# Module_ESP32.net
KiCad netlist of a schematic drawn in Altium Designer
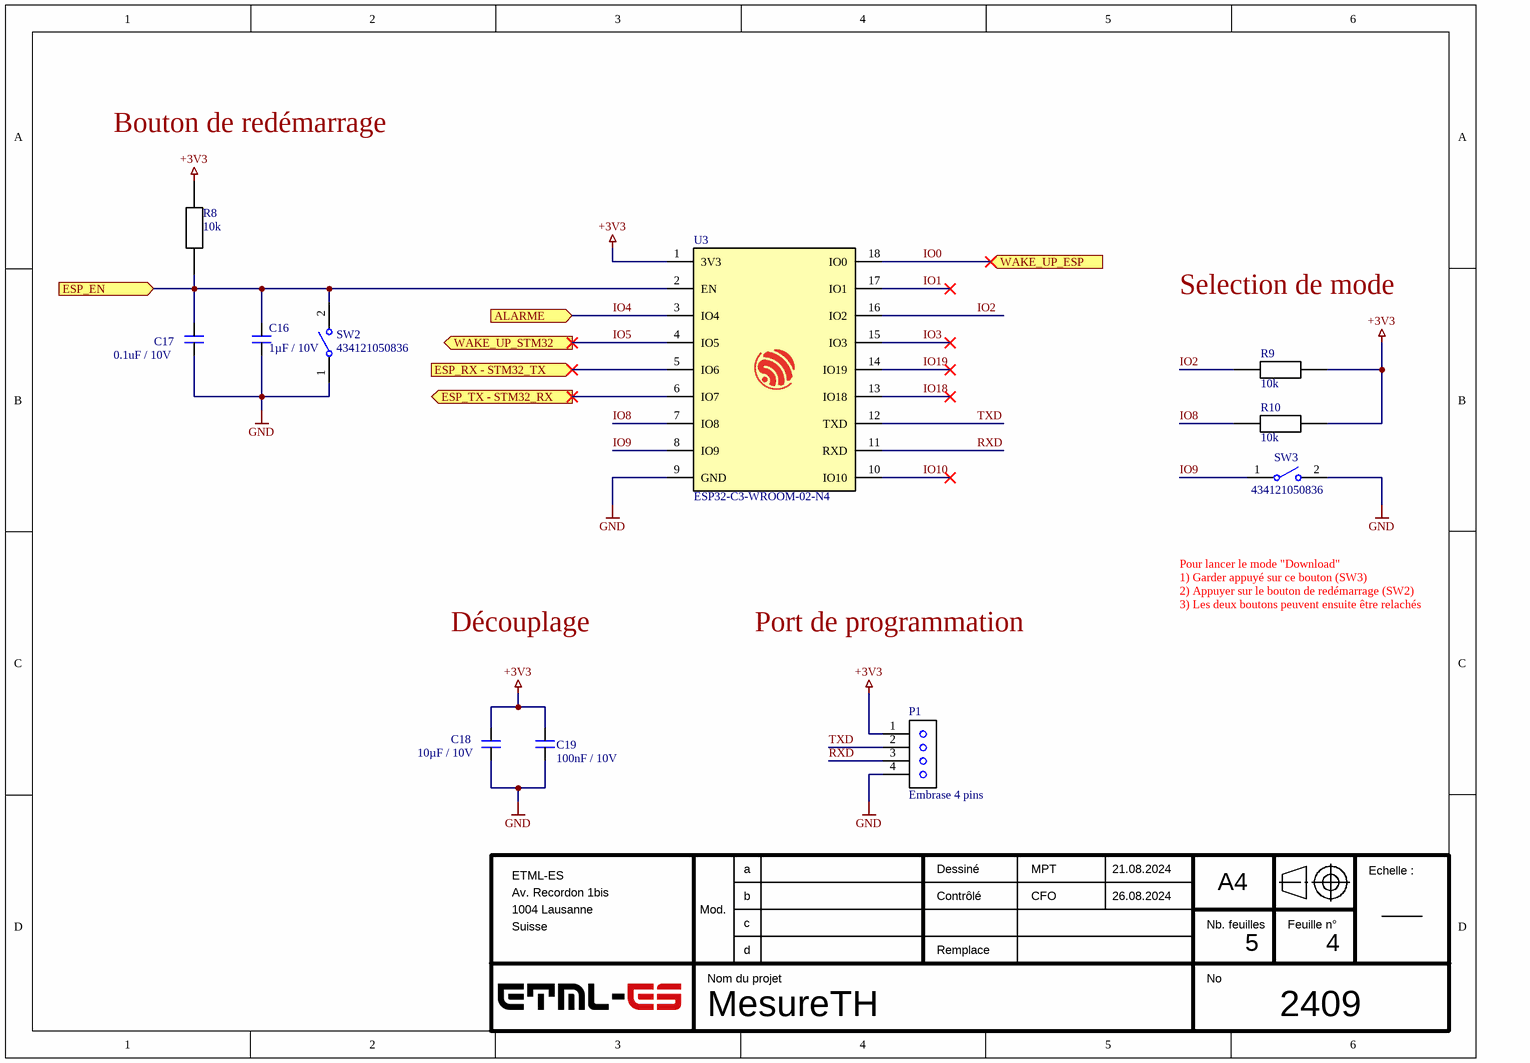
[diagram p0: Module ESP32.SchDoc]

(export (version "E")
  (design (tool "Eeschema 10.0.6"))
  (components
    (comp (ref "C16")
      (value "1µF / 10V")
      (footprint "WCAP-CSGP_0805_L2W1.25H0.8_Wave")
      (libsource (lib "Composants_Projet_2409") (part "CAPA"))
    )
    (comp (ref "C17")
      (value "0.1uF / 10V")
      (footprint "WCAP-CSGP_0805_L2W1.25H0.8_Wave")
      (libsource (lib "Composants_Projet_2409") (part "CAPA"))
    )
    (comp (ref "C18")
      (value "10µF / 10V")
      (footprint "WCAP-CSGP_0805_L2W1.25H0.8_Wave")
      (libsource (lib "Composants_Projet_2409") (part "CAPA"))
    )
    (comp (ref "C19")
      (value "100nF / 10V")
      (footprint "WCAP-CSGP_0805_L2W1.25H0.8_Wave")
      (libsource (lib "Composants_Projet_2409") (part "CAPA"))
    )
    (comp (ref "P1")
      (value "Embrase 4 pins")
      (footprint "1x4")
      (libsource (lib "Composants_Projet_2409") (part "Embrase 4 pins"))
    )
    (comp (ref "R8")
      (value "10k")
      (footprint "WRIS-PSMB_0805_L2W1.25H0.35")
      (libsource (lib "") (part "Resistance_1"))
    )
    (comp (ref "R9")
      (value "10k")
      (footprint "WRIS-PSMB_0805_L2W1.25H0.35")
      (libsource (lib "Composants_Projet_2409") (part "Resistance"))
    )
    (comp (ref "R10")
      (value "10k")
      (footprint "WRIS-PSMB_0805_L2W1.25H0.35")
      (libsource (lib "Composants_Projet_2409") (part "Resistance"))
    )
    (comp (ref "SW2")
      (value "434121050836")
      (footprint "WS-TASV_L6W3.5H5_4341x10508x6")
      (libsource (lib "Altium Content Vault") (part "SPST-NO_2P"))
    )
    (comp (ref "SW3")
      (value "434121050836")
      (footprint "WS-TASV_L6W3.5H5_4341x10508x6")
      (libsource (lib "Altium Content Vault") (part "SPST-NO_2P"))
    )
    (comp (ref "U3")
      (value "ESP32-C3-WROOM-02-N4")
      (footprint "ESP32-C3-WROOM-02-H4")
      (fields (field (name "MOUSER PART NUMBER") "356-ESP32C3WROOM02N4"))
      (libsource (lib "Composants_Projet_2409") (part "ESP32-C3-WROOM-02-N4"))
    )
  )
  (nets
    (net (code "1") (name "+3V3") (class "Default")
      (node (ref "C18") (pin "1") (pinfunction "+_1") (pintype "passive"))
      (node (ref "C19") (pin "1") (pinfunction "+_1") (pintype "passive"))
      (node (ref "P1") (pin "1") (pinfunction "VCC_1") (pintype "passive"))
      (node (ref "R10") (pin "2") (pinfunction "2_2") (pintype "passive"))
      (node (ref "R8") (pin "2") (pinfunction "2_2") (pintype "passive"))
      (node (ref "R9") (pin "2") (pinfunction "2_2") (pintype "passive"))
      (node (ref "U3") (pin "1") (pinfunction "3V3_1") (pintype "passive"))
    )
    (net (code "2") (name "/ESP_EN") (class "Default")
      (node (ref "C16") (pin "1") (pinfunction "+_1") (pintype "passive"))
      (node (ref "C17") (pin "1") (pinfunction "+_1") (pintype "passive"))
      (node (ref "R8") (pin "1") (pinfunction "1_1") (pintype "passive"))
      (node (ref "SW2") (pin "2") (pinfunction "2_2") (pintype "passive"))
      (node (ref "U3") (pin "2") (pinfunction "EN_2") (pintype "passive"))
    )
    (net (code "3") (name "/ESP_RX - STM32_TX") (class "Default")
      (node (ref "U3") (pin "5") (pinfunction "IO6_5") (pintype "passive+no_connect"))
    )
    (net (code "4") (name "/ESP_TX - STM32_RX") (class "Default")
      (node (ref "U3") (pin "6") (pinfunction "IO7_6") (pintype "passive+no_connect"))
    )
    (net (code "5") (name "/IO0") (class "Default")
      (node (ref "U3") (pin "18") (pinfunction "IO0_18") (pintype "passive+no_connect"))
    )
    (net (code "6") (name "/IO1") (class "Default")
      (node (ref "U3") (pin "17") (pinfunction "IO1_17") (pintype "passive+no_connect"))
    )
    (net (code "7") (name "/IO2") (class "Default")
      (node (ref "R9") (pin "1") (pinfunction "1_1") (pintype "passive"))
      (node (ref "U3") (pin "16") (pinfunction "IO2_16") (pintype "passive"))
    )
    (net (code "8") (name "/IO3") (class "Default")
      (node (ref "U3") (pin "15") (pinfunction "IO3_15") (pintype "passive+no_connect"))
    )
    (net (code "9") (name "/IO4") (class "Default")
      (node (ref "U3") (pin "3") (pinfunction "IO4_3") (pintype "passive"))
    )
    (net (code "10") (name "/IO5") (class "Default")
      (node (ref "U3") (pin "4") (pinfunction "IO5_4") (pintype "passive+no_connect"))
    )
    (net (code "11") (name "/IO8") (class "Default")
      (node (ref "R10") (pin "1") (pinfunction "1_1") (pintype "passive"))
      (node (ref "U3") (pin "7") (pinfunction "IO8_7") (pintype "passive"))
    )
    (net (code "12") (name "/IO9") (class "Default")
      (node (ref "SW3") (pin "1") (pinfunction "1_1") (pintype "passive"))
      (node (ref "U3") (pin "8") (pinfunction "IO9_8") (pintype "passive"))
    )
    (net (code "13") (name "/IO10") (class "Default")
      (node (ref "U3") (pin "10") (pinfunction "IO10_10") (pintype "passive+no_connect"))
    )
    (net (code "14") (name "/IO18") (class "Default")
      (node (ref "U3") (pin "13") (pinfunction "IO18_13") (pintype "passive+no_connect"))
    )
    (net (code "15") (name "/IO19") (class "Default")
      (node (ref "U3") (pin "14") (pinfunction "IO19_14") (pintype "passive+no_connect"))
    )
    (net (code "16") (name "/RXD") (class "Default")
      (node (ref "P1") (pin "3") (pinfunction "VCC_3") (pintype "passive"))
      (node (ref "U3") (pin "11") (pinfunction "RXD_11") (pintype "passive"))
    )
    (net (code "17") (name "/TXD") (class "Default")
      (node (ref "P1") (pin "2") (pinfunction "VCC_2") (pintype "passive"))
      (node (ref "U3") (pin "12") (pinfunction "TXD_12") (pintype "passive"))
    )
    (net (code "18") (name "GND") (class "Default")
      (node (ref "C16") (pin "2") (pinfunction "-_2") (pintype "passive"))
      (node (ref "C17") (pin "2") (pinfunction "-_2") (pintype "passive"))
      (node (ref "C18") (pin "2") (pinfunction "-_2") (pintype "passive"))
      (node (ref "C19") (pin "2") (pinfunction "-_2") (pintype "passive"))
      (node (ref "P1") (pin "4") (pinfunction "VCC_4") (pintype "passive"))
      (node (ref "SW2") (pin "1") (pinfunction "1_1") (pintype "passive"))
      (node (ref "SW3") (pin "2") (pinfunction "2_2") (pintype "passive"))
      (node (ref "U3") (pin "9") (pinfunction "GND_9") (pintype "passive"))
    )
  )
)
